# Cleaning_Robot.net
KiCad netlist of a schematic drawn in EAGLE
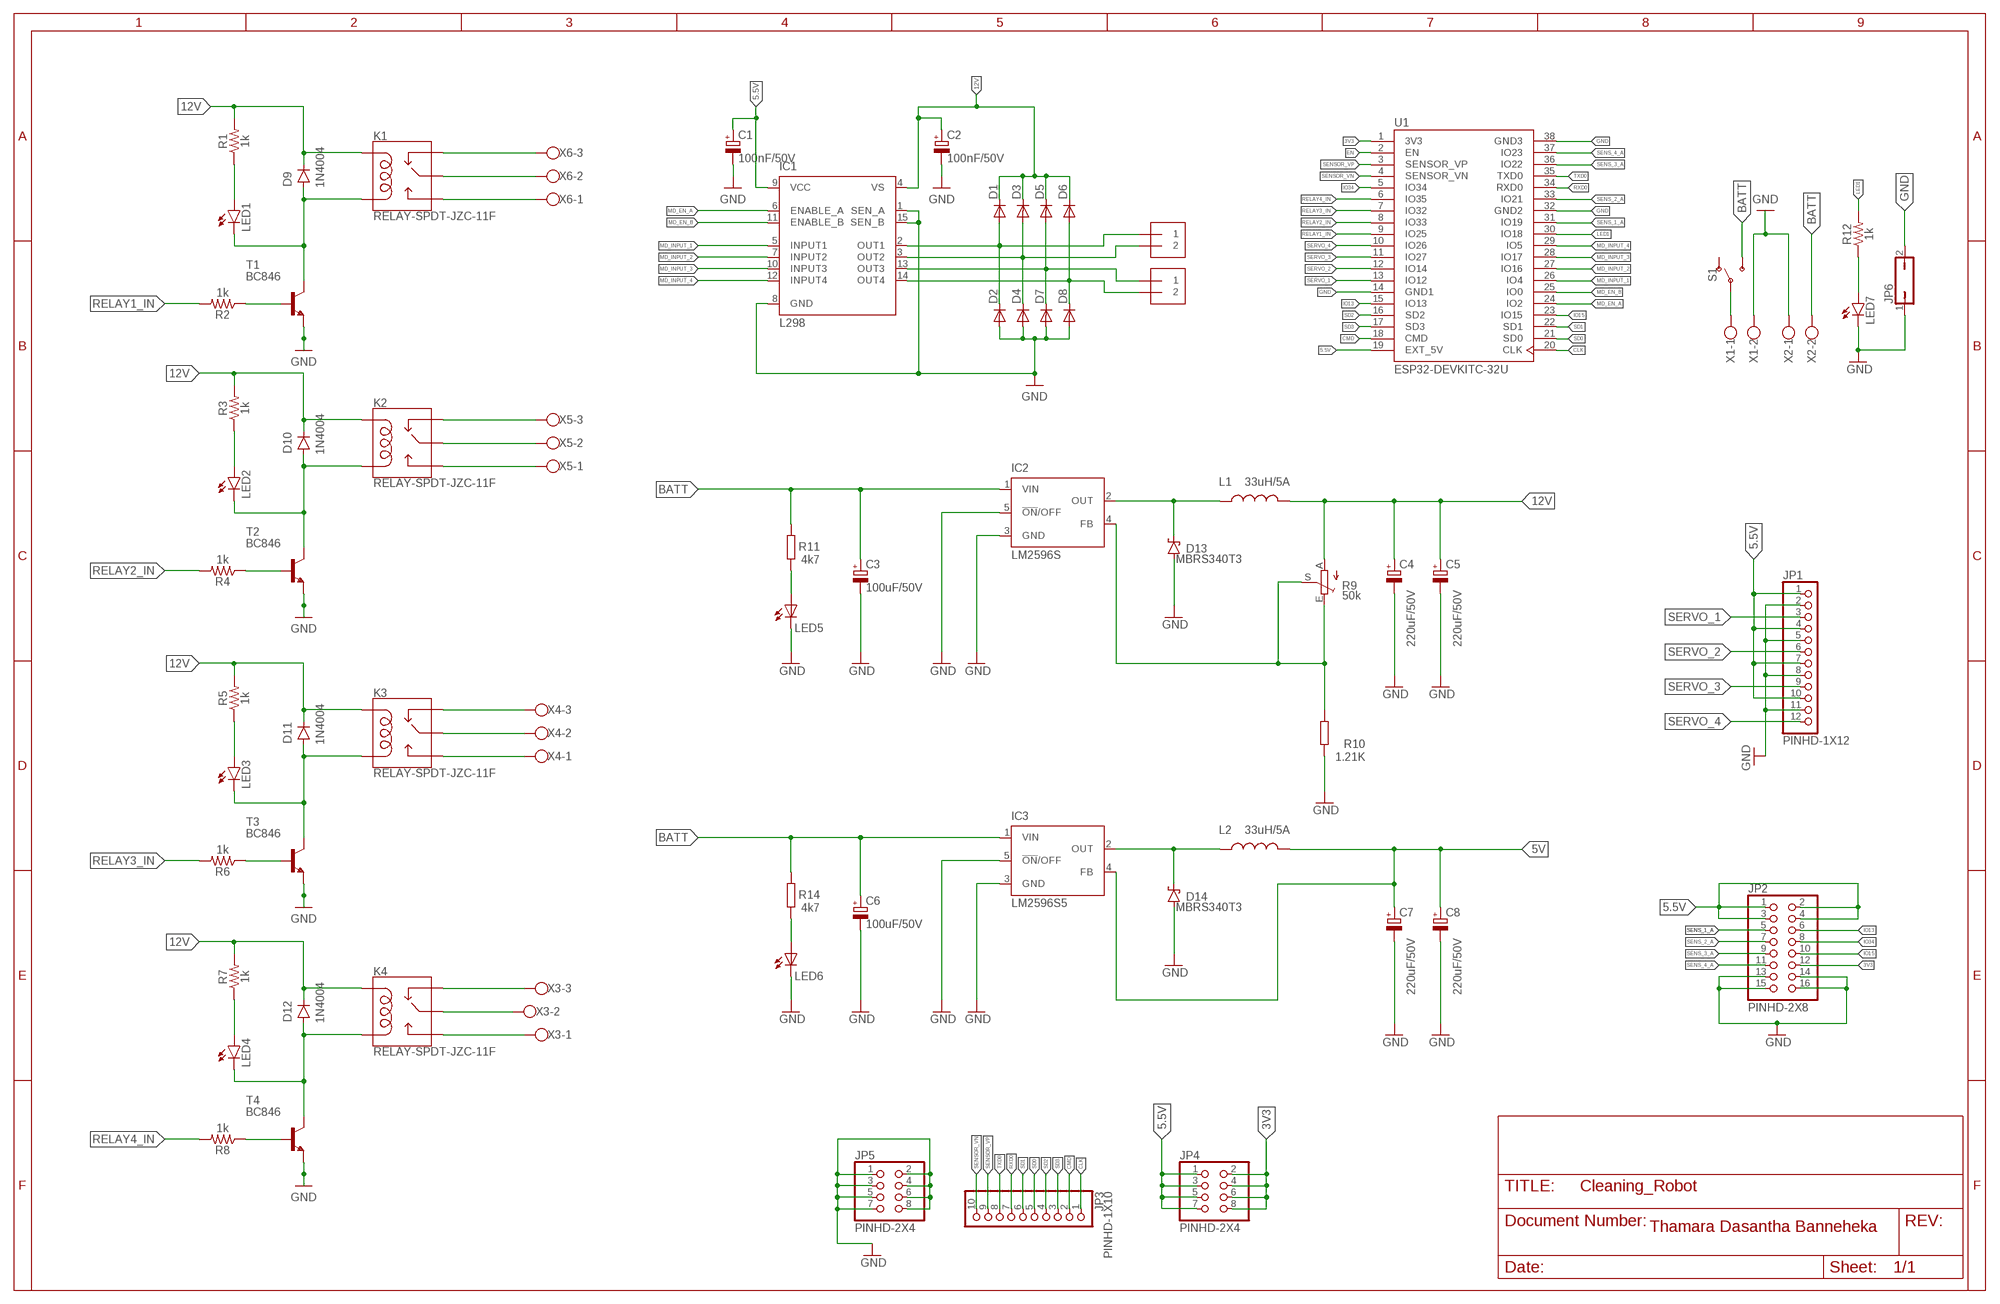
[diagram p0: schematic, sheet 1]

(export (version "E")
  (design (tool "Eeschema 10.0.6"))
  (components
    (comp (ref "C1")
      (value "100nF/50V")
      (footprint "eagle-import:153CLV-0405")
      (libsource (lib "eagle-import") (part "CPOL-EU153CLV-0405"))
    )
    (comp (ref "C2")
      (value "100nF/50V")
      (footprint "eagle-import:153CLV-0405")
      (libsource (lib "eagle-import") (part "CPOL-EU153CLV-0405"))
    )
    (comp (ref "C3")
      (value "100uF/50V")
      (footprint "eagle-import:153CLV-0810")
      (libsource (lib "eagle-import") (part "CPOL-EU153CLV-0810"))
    )
    (comp (ref "C4")
      (value "220uF/50V")
      (footprint "eagle-import:140CLH-1010")
      (libsource (lib "eagle-import") (part "CPOL-EU140CLH-1010"))
    )
    (comp (ref "C5")
      (value "220uF/50V")
      (footprint "eagle-import:140CLH-1010")
      (libsource (lib "eagle-import") (part "CPOL-EU140CLH-1010"))
    )
    (comp (ref "C6")
      (value "100uF/50V")
      (footprint "eagle-import:153CLV-0810")
      (libsource (lib "eagle-import") (part "CPOL-EU153CLV-0810"))
    )
    (comp (ref "C7")
      (value "220uF/50V")
      (footprint "eagle-import:153CLV-1010")
      (libsource (lib "eagle-import") (part "CPOL-EU153CLV-1010"))
    )
    (comp (ref "C8")
      (value "220uF/50V")
      (footprint "eagle-import:153CLV-1010")
      (libsource (lib "eagle-import") (part "CPOL-EU153CLV-1010"))
    )
    (comp (ref "D1")
      (value "DIODE-SOD123")
      (footprint "eagle-import:SOD123")
      (libsource (lib "eagle-import") (part "DIODE-SOD123"))
    )
    (comp (ref "D2")
      (value "DIODE-SOD123")
      (footprint "eagle-import:SOD123")
      (libsource (lib "eagle-import") (part "DIODE-SOD123"))
    )
    (comp (ref "D3")
      (value "DIODE-SOD123")
      (footprint "eagle-import:SOD123")
      (libsource (lib "eagle-import") (part "DIODE-SOD123"))
    )
    (comp (ref "D4")
      (value "DIODE-SOD123")
      (footprint "eagle-import:SOD123")
      (libsource (lib "eagle-import") (part "DIODE-SOD123"))
    )
    (comp (ref "D5")
      (value "DIODE-SOD123")
      (footprint "eagle-import:SOD123")
      (libsource (lib "eagle-import") (part "DIODE-SOD123"))
    )
    (comp (ref "D6")
      (value "DIODE-SOD123")
      (footprint "eagle-import:SOD123")
      (libsource (lib "eagle-import") (part "DIODE-SOD123"))
    )
    (comp (ref "D7")
      (value "DIODE-SOD123")
      (footprint "eagle-import:SOD123")
      (libsource (lib "eagle-import") (part "DIODE-SOD123"))
    )
    (comp (ref "D8")
      (value "DIODE-SOD123")
      (footprint "eagle-import:SOD123")
      (libsource (lib "eagle-import") (part "DIODE-SOD123"))
    )
    (comp (ref "D9")
      (value "1N4004")
      (footprint "eagle-import:DO-41")
      (fields
        (field (name "DIGIKEY_PART_NUMBER") "1N4004MSCT-ND")
        (field (name "MANUFACTURER") "Micro Commercial Co")
        (field (name "CREATED_BY") "PCBLayout.com")
      )
      (libsource (lib "eagle-import") (part "1N4004"))
    )
    (comp (ref "D10")
      (value "1N4004")
      (footprint "eagle-import:DO-41")
      (fields
        (field (name "DIGIKEY_PART_NUMBER") "1N4004MSCT-ND")
        (field (name "MANUFACTURER") "Micro Commercial Co")
        (field (name "CREATED_BY") "PCBLayout.com")
      )
      (libsource (lib "eagle-import") (part "1N4004"))
    )
    (comp (ref "D11")
      (value "1N4004")
      (footprint "eagle-import:DO-41")
      (fields
        (field (name "DIGIKEY_PART_NUMBER") "1N4004MSCT-ND")
        (field (name "MANUFACTURER") "Micro Commercial Co")
        (field (name "CREATED_BY") "PCBLayout.com")
      )
      (libsource (lib "eagle-import") (part "1N4004"))
    )
    (comp (ref "D12")
      (value "1N4004")
      (footprint "eagle-import:DO-41")
      (fields
        (field (name "DIGIKEY_PART_NUMBER") "1N4004MSCT-ND")
        (field (name "MANUFACTURER") "Micro Commercial Co")
        (field (name "CREATED_BY") "PCBLayout.com")
      )
      (libsource (lib "eagle-import") (part "1N4004"))
    )
    (comp (ref "D13")
      (value "MBRS340T3")
      (footprint "eagle-import:SMC")
      (libsource (lib "eagle-import") (part "MBRS30T34"))
    )
    (comp (ref "D14")
      (value "MBRS340T3")
      (footprint "eagle-import:SMC")
      (libsource (lib "eagle-import") (part "MBRS30T34"))
    )
    (comp (ref "IC1")
      (value "L298")
      (footprint "eagle-import:MULTIWATT-15")
      (fields (field (name "MPN") "L298N"))
      (libsource (lib "eagle-import") (part "L298"))
    )
    (comp (ref "IC2")
      (value "LM2596S")
      (footprint "eagle-import:TO263-5")
      (fields (field (name "MF") "NATIONAL SEMICONDUCTOR") (field (name "MPN") "LM2596S-ADJ/NOPB"))
      (libsource (lib "eagle-import") (part "LM2596S"))
    )
    (comp (ref "IC3")
      (value "LM2596S5")
      (footprint "eagle-import:TO263-5")
      (fields (field (name "MF") "NATIONAL SEMICONDUCTOR") (field (name "MPN") "LM2596S-ADJ/NOPB"))
      (libsource (lib "eagle-import") (part "LM2596S"))
    )
    (comp (ref "J2")
      (value "1X2-3.5MM")
      (footprint "eagle-import:1X2-3.5MM")
      (libsource (lib "eagle-import") (part "1X2-3.5MM"))
    )
    (comp (ref "J3")
      (value "1X2-3.5MM")
      (footprint "eagle-import:1X2-3.5MM")
      (libsource (lib "eagle-import") (part "1X2-3.5MM"))
    )
    (comp (ref "JP1")
      (value "PINHD-1X12")
      (footprint "eagle-import:1X12")
      (libsource (lib "eagle-import") (part "PINHD-1X12"))
    )
    (comp (ref "JP2")
      (value "PINHD-2X8")
      (footprint "eagle-import:2X08")
      (libsource (lib "eagle-import") (part "PINHD-2X8"))
    )
    (comp (ref "JP3")
      (value "PINHD-1X10")
      (footprint "eagle-import:1X10")
      (fields (field (name "MANUFACTURER") "Generic"))
      (libsource (lib "eagle-import") (part "PINHD-1X10"))
    )
    (comp (ref "JP4")
      (value "PINHD-2X4")
      (footprint "eagle-import:2X04")
      (fields (field (name "MANUFACTURER") "Generic"))
      (libsource (lib "eagle-import") (part "PINHD-2X4"))
    )
    (comp (ref "JP5")
      (value "PINHD-2X4")
      (footprint "eagle-import:2X04")
      (fields (field (name "MANUFACTURER") "Generic"))
      (libsource (lib "eagle-import") (part "PINHD-2X4"))
    )
    (comp (ref "JP6")
      (value "JP1Q")
      (footprint "eagle-import:JP1")
      (libsource (lib "eagle-import") (part "JP1Q"))
    )
    (comp (ref "K1")
      (value "RELAY-SPDT-JZC-11F")
      (footprint "eagle-import:RELAY-JZC")
      (libsource (lib "eagle-import") (part "RELAY-SPDT-JZC-11F"))
    )
    (comp (ref "K2")
      (value "RELAY-SPDT-JZC-11F")
      (footprint "eagle-import:RELAY-JZC")
      (libsource (lib "eagle-import") (part "RELAY-SPDT-JZC-11F"))
    )
    (comp (ref "K3")
      (value "RELAY-SPDT-JZC-11F")
      (footprint "eagle-import:RELAY-JZC")
      (libsource (lib "eagle-import") (part "RELAY-SPDT-JZC-11F"))
    )
    (comp (ref "K4")
      (value "RELAY-SPDT-JZC-11F")
      (footprint "eagle-import:RELAY-JZC")
      (libsource (lib "eagle-import") (part "RELAY-SPDT-JZC-11F"))
    )
    (comp (ref "L1")
      (value "33uH/5A")
      (footprint "eagle-import:CDRH125")
      (libsource (lib "eagle-import") (part "INDUCTORPWR"))
    )
    (comp (ref "L2")
      (value "33uH/5A")
      (footprint "eagle-import:CDRH125")
      (libsource (lib "eagle-import") (part "INDUCTORPWR"))
    )
    (comp (ref "LED1")
      (value "LEDCHIP-LED0805")
      (footprint "eagle-import:CHIP-LED0805")
      (libsource (lib "eagle-import") (part "led_259_LEDCHIP-LED0805"))
    )
    (comp (ref "LED2")
      (value "LEDCHIP-LED0805")
      (footprint "eagle-import:CHIP-LED0805")
      (libsource (lib "eagle-import") (part "led_259_LEDCHIP-LED0805"))
    )
    (comp (ref "LED3")
      (value "LEDCHIP-LED0805")
      (footprint "eagle-import:CHIP-LED0805")
      (libsource (lib "eagle-import") (part "led_259_LEDCHIP-LED0805"))
    )
    (comp (ref "LED4")
      (value "LEDCHIP-LED0805")
      (footprint "eagle-import:CHIP-LED0805")
      (libsource (lib "eagle-import") (part "led_259_LEDCHIP-LED0805"))
    )
    (comp (ref "LED5")
      (value "LEDCHIPLED_0805")
      (footprint "eagle-import:CHIPLED_0805")
      (libsource (lib "eagle-import") (part "LEDCHIPLED_0805"))
    )
    (comp (ref "LED6")
      (value "LEDCHIPLED_0805")
      (footprint "eagle-import:CHIPLED_0805")
      (libsource (lib "eagle-import") (part "LEDCHIPLED_0805"))
    )
    (comp (ref "LED7")
      (value "LEDCHIP-LED0805")
      (footprint "eagle-import:CHIP-LED0805")
      (libsource (lib "eagle-import") (part "led_259_LEDCHIP-LED0805"))
    )
    (comp (ref "R1")
      (value "1k")
      (footprint "eagle-import:0805")
      (libsource (lib "eagle-import") (part "RESISTOR0805"))
    )
    (comp (ref "R2")
      (value "1k")
      (footprint "eagle-import:0805")
      (libsource (lib "eagle-import") (part "RESISTOR0805"))
    )
    (comp (ref "R3")
      (value "1k")
      (footprint "eagle-import:0805")
      (libsource (lib "eagle-import") (part "RESISTOR0805"))
    )
    (comp (ref "R4")
      (value "1k")
      (footprint "eagle-import:0805")
      (libsource (lib "eagle-import") (part "RESISTOR0805"))
    )
    (comp (ref "R5")
      (value "1k")
      (footprint "eagle-import:0805")
      (libsource (lib "eagle-import") (part "RESISTOR0805"))
    )
    (comp (ref "R6")
      (value "1k")
      (footprint "eagle-import:0805")
      (libsource (lib "eagle-import") (part "RESISTOR0805"))
    )
    (comp (ref "R7")
      (value "1k")
      (footprint "eagle-import:0805")
      (libsource (lib "eagle-import") (part "RESISTOR0805"))
    )
    (comp (ref "R8")
      (value "1k")
      (footprint "eagle-import:0805")
      (libsource (lib "eagle-import") (part "RESISTOR0805"))
    )
    (comp (ref "R9")
      (value "50k")
      (footprint "eagle-import:S64W")
      (libsource (lib "eagle-import") (part "TRIM_EU-S64W"))
    )
    (comp (ref "R10")
      (value "1.21K")
      (footprint "eagle-import:R0805")
      (libsource (lib "eagle-import") (part "R-EU_R0805"))
    )
    (comp (ref "R11")
      (value "4k7")
      (footprint "eagle-import:R0805")
      (libsource (lib "eagle-import") (part "R-EU_R0805"))
    )
    (comp (ref "R12")
      (value "1k")
      (footprint "eagle-import:0805")
      (libsource (lib "eagle-import") (part "RESISTOR0805"))
    )
    (comp (ref "R14")
      (value "4k7")
      (footprint "eagle-import:R0805")
      (libsource (lib "eagle-import") (part "R-EU_R0805"))
    )
    (comp (ref "S1")
      (value "SWITCH-SPDT-PTH-11.6X4.0MM-KIT")
      (footprint "eagle-import:SWITCH_SPDT_PTH_11.6X4.0MM_KIT")
      (libsource (lib "eagle-import") (part "SWITCH-SPDT-PTH-11.6X4.0MM-KIT"))
    )
    (comp (ref "T1")
      (value "BC846")
      (footprint "eagle-import:SOT23")
      (libsource (lib "eagle-import") (part "BC846"))
    )
    (comp (ref "T2")
      (value "BC846")
      (footprint "eagle-import:SOT23")
      (libsource (lib "eagle-import") (part "BC846"))
    )
    (comp (ref "T3")
      (value "BC846")
      (footprint "eagle-import:SOT23")
      (libsource (lib "eagle-import") (part "BC846"))
    )
    (comp (ref "T4")
      (value "BC846")
      (footprint "eagle-import:SOT23")
      (libsource (lib "eagle-import") (part "BC846"))
    )
    (comp (ref "U1")
      (value "ESP32-DEVKITC-32U")
      (footprint "eagle-import:MODULE_ESP32-DEVKITC-32U")
      (fields (field (name "MF") "Espressif Systems"))
      (libsource (lib "eagle-import") (part "ESP32-DEVKITC-32U"))
    )
    (comp (ref "X1")
      (value "W237-102")
      (footprint "eagle-import:W237-102")
      (fields (field (name "MPN") "237-102"))
      (libsource (lib "eagle-import") (part "W237-102"))
    )
    (comp (ref "X2")
      (value "W237-102")
      (footprint "eagle-import:W237-102")
      (fields (field (name "MPN") "237-102"))
      (libsource (lib "eagle-import") (part "W237-102"))
    )
    (comp (ref "X3")
      (value "W237-103")
      (footprint "eagle-import:W237-103")
      (fields (field (name "MPN") "237-103"))
      (libsource (lib "eagle-import") (part "W237-103"))
    )
    (comp (ref "X4")
      (value "W237-103")
      (footprint "eagle-import:W237-103")
      (fields (field (name "MPN") "237-103"))
      (libsource (lib "eagle-import") (part "W237-103"))
    )
    (comp (ref "X5")
      (value "W237-103")
      (footprint "eagle-import:W237-103")
      (fields (field (name "MPN") "237-103"))
      (libsource (lib "eagle-import") (part "W237-103"))
    )
    (comp (ref "X6")
      (value "W237-103")
      (footprint "eagle-import:W237-103")
      (fields (field (name "MPN") "237-103"))
      (libsource (lib "eagle-import") (part "W237-103"))
    )
  )
  (nets
    (net (code "1") (name "/COM") (class "Default")
      (node (ref "K1") (pin "4") (pinfunction "MAIN_4") (pintype "bidirectional"))
      (node (ref "K2") (pin "4") (pinfunction "MAIN_4") (pintype "bidirectional"))
      (node (ref "K3") (pin "4") (pinfunction "MAIN_4") (pintype "bidirectional"))
      (node (ref "X4") (pin "2") (pinfunction "KL_2") (pintype "passive"))
      (node (ref "X5") (pin "2") (pinfunction "KL_2") (pintype "passive"))
      (node (ref "X6") (pin "2") (pinfunction "KL_2") (pintype "passive"))
    )
    (net (code "2") (name "/NC") (class "Default")
      (node (ref "K1") (pin "2") (pinfunction "NC_2") (pintype "bidirectional"))
      (node (ref "K2") (pin "2") (pinfunction "NC_2") (pintype "bidirectional"))
      (node (ref "K3") (pin "2") (pinfunction "NC_2") (pintype "bidirectional"))
      (node (ref "X4") (pin "3") (pinfunction "KL_3") (pintype "passive"))
      (node (ref "X5") (pin "3") (pinfunction "KL_3") (pintype "passive"))
      (node (ref "X6") (pin "3") (pinfunction "KL_3") (pintype "passive"))
    )
    (net (code "3") (name "/NO") (class "Default")
      (node (ref "K1") (pin "3") (pinfunction "NO_3") (pintype "bidirectional"))
      (node (ref "K2") (pin "3") (pinfunction "NO_3") (pintype "bidirectional"))
      (node (ref "K3") (pin "3") (pinfunction "NO_3") (pintype "bidirectional"))
      (node (ref "X4") (pin "1") (pinfunction "KL_1") (pintype "passive"))
      (node (ref "X5") (pin "1") (pinfunction "KL_1") (pintype "passive"))
      (node (ref "X6") (pin "1") (pinfunction "KL_1") (pintype "passive"))
    )
    (net (code "4") (name "3V3") (class "Default")
      (node (ref "JP2") (pin "12") (pinfunction "12_12") (pintype "passive"))
      (node (ref "JP4") (pin "2") (pinfunction "2_2") (pintype "passive"))
      (node (ref "JP4") (pin "4") (pinfunction "4_4") (pintype "passive"))
      (node (ref "JP4") (pin "6") (pinfunction "6_6") (pintype "passive"))
      (node (ref "JP4") (pin "8") (pinfunction "8_8") (pintype "passive"))
      (node (ref "U1") (pin "1") (pinfunction "3V3_1") (pintype "power_in"))
    )
    (net (code "5") (name "5.5V") (class "Default")
      (node (ref "C1") (pin "+") (pinfunction "+_+") (pintype "passive"))
      (node (ref "IC1") (pin "9") (pinfunction "VCC_9") (pintype "power_in"))
      (node (ref "JP1") (pin "1") (pinfunction "1_1") (pintype "passive"))
      (node (ref "JP1") (pin "10") (pinfunction "10_10") (pintype "passive"))
      (node (ref "JP1") (pin "4") (pinfunction "4_4") (pintype "passive"))
      (node (ref "JP1") (pin "7") (pinfunction "7_7") (pintype "passive"))
      (node (ref "JP2") (pin "1") (pinfunction "1_1") (pintype "passive"))
      (node (ref "JP2") (pin "2") (pinfunction "2_2") (pintype "passive"))
      (node (ref "JP2") (pin "3") (pinfunction "3_3") (pintype "passive"))
      (node (ref "JP2") (pin "4") (pinfunction "4_4") (pintype "passive"))
      (node (ref "JP4") (pin "1") (pinfunction "1_1") (pintype "passive"))
      (node (ref "JP4") (pin "3") (pinfunction "3_3") (pintype "passive"))
      (node (ref "JP4") (pin "5") (pinfunction "5_5") (pintype "passive"))
      (node (ref "JP4") (pin "7") (pinfunction "7_7") (pintype "passive"))
      (node (ref "U1") (pin "19") (pinfunction "EXT_5V_19") (pintype "power_in"))
    )
    (net (code "6") (name "5V") (class "Default")
      (node (ref "C7") (pin "+") (pinfunction "+_+") (pintype "passive"))
      (node (ref "C8") (pin "+") (pinfunction "+_+") (pintype "passive"))
      (node (ref "IC3") (pin "4") (pinfunction "FB_4") (pintype "input"))
      (node (ref "L2") (pin "2") (pinfunction "2_2") (pintype "passive"))
    )
    (net (code "7") (name "12V") (class "Default")
      (node (ref "C2") (pin "+") (pinfunction "+_+") (pintype "passive"))
      (node (ref "C4") (pin "+") (pinfunction "+_+") (pintype "passive"))
      (node (ref "C5") (pin "+") (pinfunction "+_+") (pintype "passive"))
      (node (ref "D1") (pin "C") (pinfunction "C_C") (pintype "passive"))
      (node (ref "D10") (pin "C") (pinfunction "C_C") (pintype "passive"))
      (node (ref "D11") (pin "C") (pinfunction "C_C") (pintype "passive"))
      (node (ref "D12") (pin "C") (pinfunction "C_C") (pintype "passive"))
      (node (ref "D3") (pin "C") (pinfunction "C_C") (pintype "passive"))
      (node (ref "D5") (pin "C") (pinfunction "C_C") (pintype "passive"))
      (node (ref "D6") (pin "C") (pinfunction "C_C") (pintype "passive"))
      (node (ref "D9") (pin "C") (pinfunction "C_C") (pintype "passive"))
      (node (ref "IC1") (pin "4") (pinfunction "VS_4") (pintype "power_in"))
      (node (ref "K1") (pin "5") (pinfunction "COIL1_5") (pintype "bidirectional"))
      (node (ref "K2") (pin "5") (pinfunction "COIL1_5") (pintype "bidirectional"))
      (node (ref "K3") (pin "5") (pinfunction "COIL1_5") (pintype "bidirectional"))
      (node (ref "K4") (pin "5") (pinfunction "COIL1_5") (pintype "bidirectional"))
      (node (ref "L1") (pin "2") (pinfunction "2_2") (pintype "passive"))
      (node (ref "R1") (pin "2") (pinfunction "2_2") (pintype "passive"))
      (node (ref "R3") (pin "2") (pinfunction "2_2") (pintype "passive"))
      (node (ref "R5") (pin "2") (pinfunction "2_2") (pintype "passive"))
      (node (ref "R7") (pin "2") (pinfunction "2_2") (pintype "passive"))
      (node (ref "R9") (pin "A") (pinfunction "A_A") (pintype "passive"))
    )
    (net (code "8") (name "BATT") (class "Default")
      (node (ref "C3") (pin "+") (pinfunction "+_+") (pintype "passive"))
      (node (ref "C6") (pin "+") (pinfunction "+_+") (pintype "passive"))
      (node (ref "IC2") (pin "1") (pinfunction "VIN_1") (pintype "input"))
      (node (ref "IC3") (pin "1") (pinfunction "VIN_1") (pintype "input"))
      (node (ref "R11") (pin "2") (pinfunction "2_2") (pintype "passive"))
      (node (ref "R14") (pin "2") (pinfunction "2_2") (pintype "passive"))
      (node (ref "S1") (pin "3") (pinfunction "S_3") (pintype "passive"))
      (node (ref "X2") (pin "2") (pinfunction "KL_2") (pintype "passive"))
    )
    (net (code "9") (name "CLK") (class "Default")
      (node (ref "JP3") (pin "1") (pinfunction "1_1") (pintype "passive"))
      (node (ref "U1") (pin "20") (pinfunction "CLK_20") (pintype "input"))
    )
    (net (code "10") (name "CMD") (class "Default")
      (node (ref "JP3") (pin "2") (pinfunction "2_2") (pintype "passive"))
      (node (ref "U1") (pin "18") (pinfunction "CMD_18") (pintype "bidirectional"))
    )
    (net (code "11") (name "EN") (class "Default")
      (node (ref "U1") (pin "2") (pinfunction "EN_2") (pintype "input"))
    )
    (net (code "12") (name "GND") (class "Default")
      (node (ref "C1") (pin "-") (pinfunction "-_-") (pintype "passive"))
      (node (ref "C2") (pin "-") (pinfunction "-_-") (pintype "passive"))
      (node (ref "C3") (pin "-") (pinfunction "-_-") (pintype "passive"))
      (node (ref "C4") (pin "-") (pinfunction "-_-") (pintype "passive"))
      (node (ref "C5") (pin "-") (pinfunction "-_-") (pintype "passive"))
      (node (ref "C6") (pin "-") (pinfunction "-_-") (pintype "passive"))
      (node (ref "C7") (pin "-") (pinfunction "-_-") (pintype "passive"))
      (node (ref "C8") (pin "-") (pinfunction "-_-") (pintype "passive"))
      (node (ref "D13") (pin "A") (pinfunction "A_A") (pintype "passive"))
      (node (ref "D14") (pin "A") (pinfunction "A_A") (pintype "passive"))
      (node (ref "D2") (pin "A") (pinfunction "A_A") (pintype "passive"))
      (node (ref "D4") (pin "A") (pinfunction "A_A") (pintype "passive"))
      (node (ref "D7") (pin "A") (pinfunction "A_A") (pintype "passive"))
      (node (ref "D8") (pin "A") (pinfunction "A_A") (pintype "passive"))
      (node (ref "IC1") (pin "1") (pinfunction "SEN_A_1") (pintype "input"))
      (node (ref "IC1") (pin "15") (pinfunction "SEN_B_15") (pintype "input"))
      (node (ref "IC1") (pin "8") (pinfunction "GND_8") (pintype "power_in"))
      (node (ref "IC2") (pin "3") (pinfunction "GND_3") (pintype "power_in"))
      (node (ref "IC2") (pin "5") (pinfunction "~{ON}/OFF_5") (pintype "input"))
      (node (ref "IC3") (pin "3") (pinfunction "GND_3") (pintype "power_in"))
      (node (ref "IC3") (pin "5") (pinfunction "~{ON}/OFF_5") (pintype "input"))
      (node (ref "JP1") (pin "11") (pinfunction "11_11") (pintype "passive"))
      (node (ref "JP1") (pin "2") (pinfunction "2_2") (pintype "passive"))
      (node (ref "JP1") (pin "5") (pinfunction "5_5") (pintype "passive"))
      (node (ref "JP1") (pin "8") (pinfunction "8_8") (pintype "passive"))
      (node (ref "JP2") (pin "13") (pinfunction "13_13") (pintype "passive"))
      (node (ref "JP2") (pin "14") (pinfunction "14_14") (pintype "passive"))
      (node (ref "JP2") (pin "15") (pinfunction "15_15") (pintype "passive"))
      (node (ref "JP2") (pin "16") (pinfunction "16_16") (pintype "passive"))
      (node (ref "JP5") (pin "1") (pinfunction "1_1") (pintype "passive"))
      (node (ref "JP5") (pin "2") (pinfunction "2_2") (pintype "passive"))
      (node (ref "JP5") (pin "3") (pinfunction "3_3") (pintype "passive"))
      (node (ref "JP5") (pin "4") (pinfunction "4_4") (pintype "passive"))
      (node (ref "JP5") (pin "5") (pinfunction "5_5") (pintype "passive"))
      (node (ref "JP5") (pin "6") (pinfunction "6_6") (pintype "passive"))
      (node (ref "JP5") (pin "7") (pinfunction "7_7") (pintype "passive"))
      (node (ref "JP5") (pin "8") (pinfunction "8_8") (pintype "passive"))
      (node (ref "JP6") (pin "1") (pinfunction "1_1") (pintype "passive"))
      (node (ref "JP6") (pin "2") (pinfunction "2_2") (pintype "passive"))
      (node (ref "LED5") (pin "C") (pinfunction "C_C") (pintype "passive"))
      (node (ref "LED6") (pin "C") (pinfunction "C_C") (pintype "passive"))
      (node (ref "LED7") (pin "C") (pinfunction "C_C") (pintype "passive"))
      (node (ref "R10") (pin "1") (pinfunction "1_1") (pintype "passive"))
      (node (ref "T1") (pin "2") (pinfunction "E_2") (pintype "passive"))
      (node (ref "T2") (pin "2") (pinfunction "E_2") (pintype "passive"))
      (node (ref "T3") (pin "2") (pinfunction "E_2") (pintype "passive"))
      (node (ref "T4") (pin "2") (pinfunction "E_2") (pintype "passive"))
      (node (ref "U1") (pin "14") (pinfunction "GND1_14") (pintype "power_in"))
      (node (ref "U1") (pin "32") (pinfunction "GND2_32") (pintype "power_in"))
      (node (ref "U1") (pin "38") (pinfunction "GND3_38") (pintype "power_in"))
      (node (ref "X1") (pin "2") (pinfunction "KL_2") (pintype "passive"))
      (node (ref "X2") (pin "1") (pinfunction "KL_1") (pintype "passive"))
    )
    (net (code "13") (name "IO13") (class "Default")
      (node (ref "JP2") (pin "6") (pinfunction "6_6") (pintype "passive"))
      (node (ref "U1") (pin "15") (pinfunction "IO13_15") (pintype "bidirectional"))
    )
    (net (code "14") (name "IO15") (class "Default")
      (node (ref "JP2") (pin "10") (pinfunction "10_10") (pintype "passive"))
      (node (ref "U1") (pin "23") (pinfunction "IO15_23") (pintype "bidirectional"))
    )
    (net (code "15") (name "IO34") (class "Default")
      (node (ref "JP2") (pin "8") (pinfunction "8_8") (pintype "passive"))
      (node (ref "U1") (pin "5") (pinfunction "IO34_5") (pintype "bidirectional"))
    )
    (net (code "16") (name "LED1") (class "Default")
      (node (ref "R12") (pin "2") (pinfunction "2_2") (pintype "passive"))
      (node (ref "U1") (pin "30") (pinfunction "IO18_30") (pintype "bidirectional"))
    )
    (net (code "17") (name "MD_EN_A") (class "Default")
      (node (ref "IC1") (pin "6") (pinfunction "ENABLE_A_6") (pintype "input"))
      (node (ref "U1") (pin "24") (pinfunction "IO2_24") (pintype "bidirectional"))
    )
    (net (code "18") (name "MD_EN_B") (class "Default")
      (node (ref "IC1") (pin "11") (pinfunction "ENABLE_B_11") (pintype "input"))
      (node (ref "U1") (pin "25") (pinfunction "IO0_25") (pintype "bidirectional"))
    )
    (net (code "19") (name "MD_INPUT_1") (class "Default")
      (node (ref "IC1") (pin "5") (pinfunction "INPUT1_5") (pintype "input"))
      (node (ref "U1") (pin "26") (pinfunction "IO4_26") (pintype "bidirectional"))
    )
    (net (code "20") (name "MD_INPUT_2") (class "Default")
      (node (ref "IC1") (pin "7") (pinfunction "INPUT2_7") (pintype "input"))
      (node (ref "U1") (pin "27") (pinfunction "IO16_27") (pintype "bidirectional"))
    )
    (net (code "21") (name "MD_INPUT_3") (class "Default")
      (node (ref "IC1") (pin "10") (pinfunction "INPUT3_10") (pintype "input"))
      (node (ref "U1") (pin "28") (pinfunction "IO17_28") (pintype "bidirectional"))
    )
    (net (code "22") (name "MD_INPUT_4") (class "Default")
      (node (ref "IC1") (pin "12") (pinfunction "INPUT4_12") (pintype "input"))
      (node (ref "U1") (pin "29") (pinfunction "IO5_29") (pintype "bidirectional"))
    )
    (net (code "23") (name "Net-(IC1-OUT1)") (class "Default")
      (node (ref "D1") (pin "A") (pinfunction "A_A") (pintype "passive"))
      (node (ref "D2") (pin "C") (pinfunction "C_C") (pintype "passive"))
      (node (ref "IC1") (pin "2") (pinfunction "OUT1_2") (pintype "output"))
      (node (ref "J2") (pin "1") (pinfunction "1_1") (pintype "passive"))
    )
    (net (code "24") (name "Net-(IC1-OUT2)") (class "Default")
      (node (ref "D3") (pin "A") (pinfunction "A_A") (pintype "passive"))
      (node (ref "D4") (pin "C") (pinfunction "C_C") (pintype "passive"))
      (node (ref "IC1") (pin "3") (pinfunction "OUT2_3") (pintype "output"))
      (node (ref "J2") (pin "2") (pinfunction "2_2") (pintype "passive"))
    )
    (net (code "25") (name "Net-(IC1-OUT3)") (class "Default")
      (node (ref "D5") (pin "A") (pinfunction "A_A") (pintype "passive"))
      (node (ref "D7") (pin "C") (pinfunction "C_C") (pintype "passive"))
      (node (ref "IC1") (pin "13") (pinfunction "OUT3_13") (pintype "output"))
      (node (ref "J3") (pin "1") (pinfunction "1_1") (pintype "passive"))
    )
    (net (code "26") (name "Net-(IC1-OUT4)") (class "Default")
      (node (ref "D6") (pin "A") (pinfunction "A_A") (pintype "passive"))
      (node (ref "D8") (pin "C") (pinfunction "C_C") (pintype "passive"))
      (node (ref "IC1") (pin "14") (pinfunction "OUT4_14") (pintype "output"))
      (node (ref "J3") (pin "2") (pinfunction "2_2") (pintype "passive"))
    )
    (net (code "27") (name "Net-(IC2-FB)") (class "Default")
      (node (ref "IC2") (pin "4") (pinfunction "FB_4") (pintype "input"))
      (node (ref "R10") (pin "2") (pinfunction "2_2") (pintype "passive"))
      (node (ref "R9") (pin "E") (pinfunction "E_E") (pintype "passive"))
      (node (ref "R9") (pin "S") (pinfunction "S_S") (pintype "passive"))
    )
    (net (code "28") (name "Net-(IC2-OUT)") (class "Default")
      (node (ref "D13") (pin "C") (pinfunction "C_C") (pintype "passive"))
      (node (ref "IC2") (pin "2") (pinfunction "OUT_2") (pintype "output"))
      (node (ref "L1") (pin "1") (pinfunction "1_1") (pintype "passive"))
    )
    (net (code "29") (name "Net-(IC3-OUT)") (class "Default")
      (node (ref "D14") (pin "C") (pinfunction "C_C") (pintype "passive"))
      (node (ref "IC3") (pin "2") (pinfunction "OUT_2") (pintype "output"))
      (node (ref "L2") (pin "1") (pinfunction "1_1") (pintype "passive"))
    )
    (net (code "30") (name "Net-(K1-COIL2)") (class "Default")
      (node (ref "D9") (pin "A") (pinfunction "A_A") (pintype "passive"))
      (node (ref "K1") (pin "1") (pinfunction "COIL2_1") (pintype "bidirectional"))
      (node (ref "LED1") (pin "C") (pinfunction "C_C") (pintype "passive"))
      (node (ref "T1") (pin "3") (pinfunction "C_3") (pintype "passive"))
    )
    (net (code "31") (name "Net-(K2-COIL2)") (class "Default")
      (node (ref "D10") (pin "A") (pinfunction "A_A") (pintype "passive"))
      (node (ref "K2") (pin "1") (pinfunction "COIL2_1") (pintype "bidirectional"))
      (node (ref "LED2") (pin "C") (pinfunction "C_C") (pintype "passive"))
      (node (ref "T2") (pin "3") (pinfunction "C_3") (pintype "passive"))
    )
    (net (code "32") (name "Net-(K3-COIL2)") (class "Default")
      (node (ref "D11") (pin "A") (pinfunction "A_A") (pintype "passive"))
      (node (ref "K3") (pin "1") (pinfunction "COIL2_1") (pintype "bidirectional"))
      (node (ref "LED3") (pin "C") (pinfunction "C_C") (pintype "passive"))
      (node (ref "T3") (pin "3") (pinfunction "C_3") (pintype "passive"))
    )
    (net (code "33") (name "Net-(K4-COIL2)") (class "Default")
      (node (ref "D12") (pin "A") (pinfunction "A_A") (pintype "passive"))
      (node (ref "K4") (pin "1") (pinfunction "COIL2_1") (pintype "bidirectional"))
      (node (ref "LED4") (pin "C") (pinfunction "C_C") (pintype "passive"))
      (node (ref "T4") (pin "3") (pinfunction "C_3") (pintype "passive"))
    )
    (net (code "34") (name "Net-(K4-MAIN)") (class "Default")
      (node (ref "K4") (pin "4") (pinfunction "MAIN_4") (pintype "bidirectional"))
      (node (ref "X3") (pin "2") (pinfunction "KL_2") (pintype "passive"))
    )
    (net (code "35") (name "Net-(K4-NC)") (class "Default")
      (node (ref "K4") (pin "2") (pinfunction "NC_2") (pintype "bidirectional"))
      (node (ref "X3") (pin "3") (pinfunction "KL_3") (pintype "passive"))
    )
    (net (code "36") (name "Net-(K4-NO)") (class "Default")
      (node (ref "K4") (pin "3") (pinfunction "NO_3") (pintype "bidirectional"))
      (node (ref "X3") (pin "1") (pinfunction "KL_1") (pintype "passive"))
    )
    (net (code "37") (name "Net-(LED1-PadA)") (class "Default")
      (node (ref "LED1") (pin "A") (pinfunction "A_A") (pintype "passive"))
      (node (ref "R1") (pin "1") (pinfunction "1_1") (pintype "passive"))
    )
    (net (code "38") (name "Net-(LED2-PadA)") (class "Default")
      (node (ref "LED2") (pin "A") (pinfunction "A_A") (pintype "passive"))
      (node (ref "R3") (pin "1") (pinfunction "1_1") (pintype "passive"))
    )
    (net (code "39") (name "Net-(LED3-PadA)") (class "Default")
      (node (ref "LED3") (pin "A") (pinfunction "A_A") (pintype "passive"))
      (node (ref "R5") (pin "1") (pinfunction "1_1") (pintype "passive"))
    )
    (net (code "40") (name "Net-(LED4-PadA)") (class "Default")
      (node (ref "LED4") (pin "A") (pinfunction "A_A") (pintype "passive"))
      (node (ref "R7") (pin "1") (pinfunction "1_1") (pintype "passive"))
    )
    (net (code "41") (name "Net-(LED5-PadA)") (class "Default")
      (node (ref "LED5") (pin "A") (pinfunction "A_A") (pintype "passive"))
      (node (ref "R11") (pin "1") (pinfunction "1_1") (pintype "passive"))
    )
    (net (code "42") (name "Net-(LED6-PadA)") (class "Default")
      (node (ref "LED6") (pin "A") (pinfunction "A_A") (pintype "passive"))
      (node (ref "R14") (pin "1") (pinfunction "1_1") (pintype "passive"))
    )
    (net (code "43") (name "Net-(LED7-PadA)") (class "Default")
      (node (ref "LED7") (pin "A") (pinfunction "A_A") (pintype "passive"))
      (node (ref "R12") (pin "1") (pinfunction "1_1") (pintype "passive"))
    )
    (net (code "44") (name "Net-(S1-P)") (class "Default")
      (node (ref "S1") (pin "2") (pinfunction "P_2") (pintype "passive"))
      (node (ref "X1") (pin "1") (pinfunction "KL_1") (pintype "passive"))
    )
    (net (code "45") (name "Net-(T1-B)") (class "Default")
      (node (ref "R2") (pin "1") (pinfunction "1_1") (pintype "passive"))
      (node (ref "T1") (pin "1") (pinfunction "B_1") (pintype "passive"))
    )
    (net (code "46") (name "Net-(T2-B)") (class "Default")
      (node (ref "R4") (pin "1") (pinfunction "1_1") (pintype "passive"))
      (node (ref "T2") (pin "1") (pinfunction "B_1") (pintype "passive"))
    )
    (net (code "47") (name "Net-(T3-B)") (class "Default")
      (node (ref "R6") (pin "1") (pinfunction "1_1") (pintype "passive"))
      (node (ref "T3") (pin "1") (pinfunction "B_1") (pintype "passive"))
    )
    (net (code "48") (name "Net-(T4-B)") (class "Default")
      (node (ref "R8") (pin "1") (pinfunction "1_1") (pintype "passive"))
      (node (ref "T4") (pin "1") (pinfunction "B_1") (pintype "passive"))
    )
    (net (code "49") (name "RELAY1_IN") (class "Default")
      (node (ref "R2") (pin "2") (pinfunction "2_2") (pintype "passive"))
      (node (ref "U1") (pin "9") (pinfunction "IO25_9") (pintype "bidirectional"))
    )
    (net (code "50") (name "RELAY2_IN") (class "Default")
      (node (ref "R4") (pin "2") (pinfunction "2_2") (pintype "passive"))
      (node (ref "U1") (pin "8") (pinfunction "IO33_8") (pintype "bidirectional"))
    )
    (net (code "51") (name "RELAY3_IN") (class "Default")
      (node (ref "R6") (pin "2") (pinfunction "2_2") (pintype "passive"))
      (node (ref "U1") (pin "7") (pinfunction "IO32_7") (pintype "bidirectional"))
    )
    (net (code "52") (name "RELAY4_IN") (class "Default")
      (node (ref "R8") (pin "2") (pinfunction "2_2") (pintype "passive"))
      (node (ref "U1") (pin "6") (pinfunction "IO35_6") (pintype "bidirectional"))
    )
    (net (code "53") (name "RXD0") (class "Default")
      (node (ref "JP3") (pin "7") (pinfunction "7_7") (pintype "passive"))
      (node (ref "U1") (pin "34") (pinfunction "RXD0_34") (pintype "input"))
    )
    (net (code "54") (name "SD0") (class "Default")
      (node (ref "JP3") (pin "5") (pinfunction "5_5") (pintype "passive"))
      (node (ref "U1") (pin "21") (pinfunction "SD0_21") (pintype "bidirectional"))
    )
    (net (code "55") (name "SD1") (class "Default")
      (node (ref "JP3") (pin "6") (pinfunction "6_6") (pintype "passive"))
      (node (ref "U1") (pin "22") (pinfunction "SD1_22") (pintype "bidirectional"))
    )
    (net (code "56") (name "SD2") (class "Default")
      (node (ref "JP3") (pin "4") (pinfunction "4_4") (pintype "passive"))
      (node (ref "U1") (pin "16") (pinfunction "SD2_16") (pintype "bidirectional"))
    )
    (net (code "57") (name "SD3") (class "Default")
      (node (ref "JP3") (pin "3") (pinfunction "3_3") (pintype "passive"))
      (node (ref "U1") (pin "17") (pinfunction "SD3_17") (pintype "bidirectional"))
    )
    (net (code "58") (name "SENSOR_VN") (class "Default")
      (node (ref "JP3") (pin "10") (pinfunction "10_10") (pintype "passive"))
      (node (ref "U1") (pin "4") (pinfunction "SENSOR_VN_4") (pintype "input"))
    )
    (net (code "59") (name "SENSOR_VP") (class "Default")
      (node (ref "JP3") (pin "9") (pinfunction "9_9") (pintype "passive"))
      (node (ref "U1") (pin "3") (pinfunction "SENSOR_VP_3") (pintype "input"))
    )
    (net (code "60") (name "SENS_1_A") (class "Default")
      (node (ref "JP2") (pin "5") (pinfunction "5_5") (pintype "passive"))
      (node (ref "U1") (pin "31") (pinfunction "IO19_31") (pintype "bidirectional"))
    )
    (net (code "61") (name "SENS_2_A") (class "Default")
      (node (ref "JP2") (pin "7") (pinfunction "7_7") (pintype "passive"))
      (node (ref "U1") (pin "33") (pinfunction "IO21_33") (pintype "bidirectional"))
    )
    (net (code "62") (name "SENS_3_A") (class "Default")
      (node (ref "JP2") (pin "9") (pinfunction "9_9") (pintype "passive"))
      (node (ref "U1") (pin "36") (pinfunction "IO22_36") (pintype "bidirectional"))
    )
    (net (code "63") (name "SENS_4_A") (class "Default")
      (node (ref "JP2") (pin "11") (pinfunction "11_11") (pintype "passive"))
      (node (ref "U1") (pin "37") (pinfunction "IO23_37") (pintype "bidirectional"))
    )
    (net (code "64") (name "SERVO_1") (class "Default")
      (node (ref "JP1") (pin "3") (pinfunction "3_3") (pintype "passive"))
      (node (ref "U1") (pin "13") (pinfunction "IO12_13") (pintype "bidirectional"))
    )
    (net (code "65") (name "SERVO_2") (class "Default")
      (node (ref "JP1") (pin "6") (pinfunction "6_6") (pintype "passive"))
      (node (ref "U1") (pin "12") (pinfunction "IO14_12") (pintype "bidirectional"))
    )
    (net (code "66") (name "SERVO_3") (class "Default")
      (node (ref "JP1") (pin "9") (pinfunction "9_9") (pintype "passive"))
      (node (ref "U1") (pin "11") (pinfunction "IO27_11") (pintype "bidirectional"))
    )
    (net (code "67") (name "SERVO_4") (class "Default")
      (node (ref "JP1") (pin "12") (pinfunction "12_12") (pintype "passive"))
      (node (ref "U1") (pin "10") (pinfunction "IO26_10") (pintype "bidirectional"))
    )
    (net (code "68") (name "TXD0") (class "Default")
      (node (ref "JP3") (pin "8") (pinfunction "8_8") (pintype "passive"))
      (node (ref "U1") (pin "35") (pinfunction "TXD0_35") (pintype "output"))
    )
    (net (code "69") (name "unconnected-(S1-O-Pad1)") (class "Default")
      (node (ref "S1") (pin "1") (pinfunction "O_1") (pintype "passive"))
    )
  )
)
